# OpenHealth.net
KiCad netlist of a schematic drawn in EAGLE
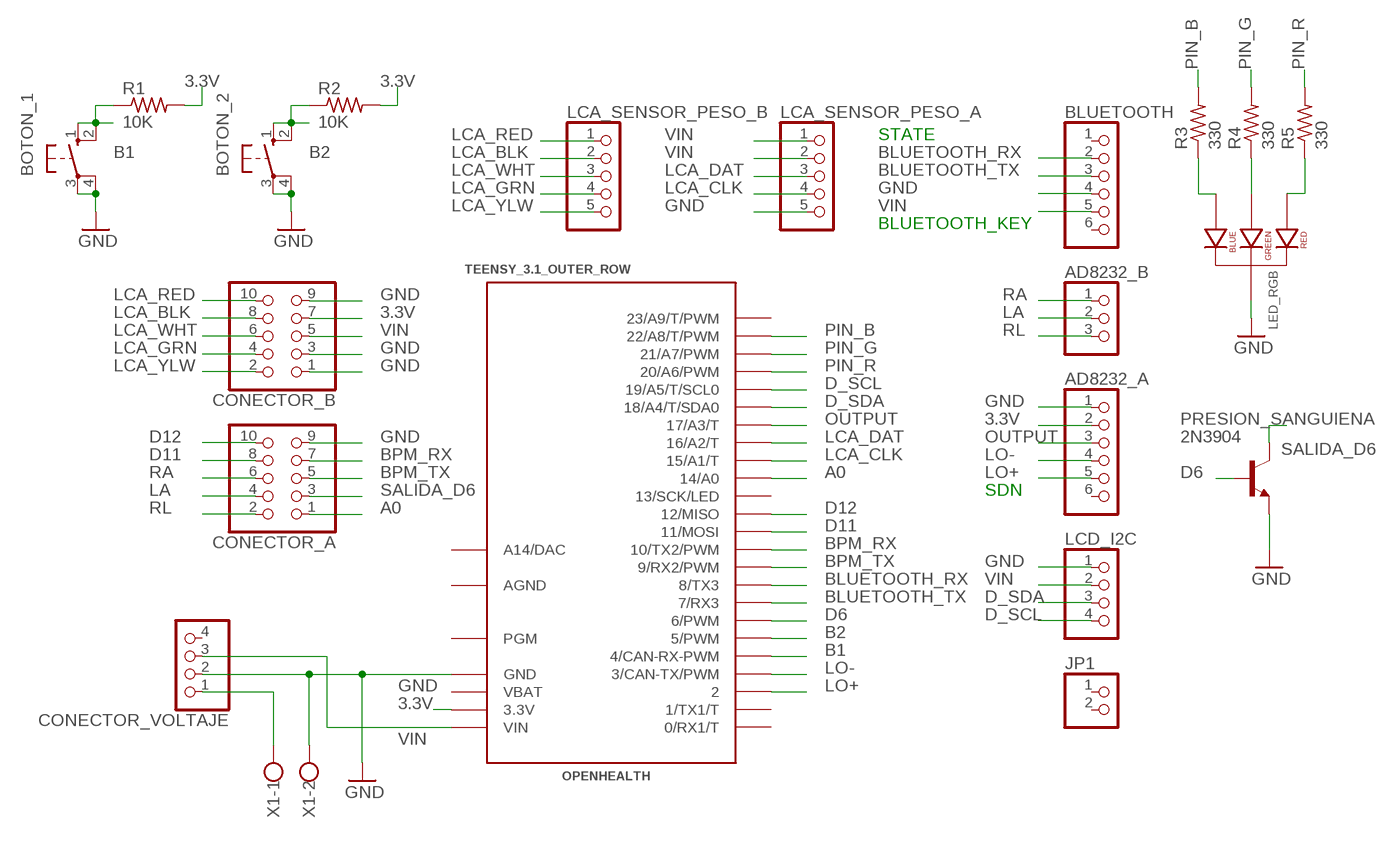
[diagram p0: schematic, sheet 1]

(export (version "E")
  (design (tool "Eeschema 10.0.6"))
  (components
    (comp (ref "AD8232_A")
      (value "PINHD-1X6")
      (footprint "eagle-import:1X06")
      (libsource (lib "eagle-import") (part "PINHD-1X6"))
    )
    (comp (ref "AD8232_B")
      (value "PINHD-1X3")
      (footprint "eagle-import:1X03")
      (libsource (lib "eagle-import") (part "PINHD-1X3"))
    )
    (comp (ref "BLUETOOTH")
      (value "PINHD-1X6")
      (footprint "eagle-import:1X06")
      (libsource (lib "eagle-import") (part "PINHD-1X6"))
    )
    (comp (ref "BOTON_1")
      (value "10-XX")
      (footprint "eagle-import:B3F-10XX")
      (fields (field (name "MPN") "B3F-1000"))
      (libsource (lib "eagle-import") (part "10-XX"))
    )
    (comp (ref "BOTON_2")
      (value "10-XX")
      (footprint "eagle-import:B3F-10XX")
      (fields (field (name "MPN") "B3F-1000"))
      (libsource (lib "eagle-import") (part "10-XX"))
    )
    (comp (ref "CONECTOR_A")
      (value "PINHD-2X5")
      (footprint "eagle-import:2X05")
      (libsource (lib "eagle-import") (part "PINHD-2X5"))
    )
    (comp (ref "CONECTOR_B")
      (value "PINHD-2X5")
      (footprint "eagle-import:2X05")
      (libsource (lib "eagle-import") (part "PINHD-2X5"))
    )
    (comp (ref "CONECTOR_VOLTAJE")
      (value "PINHD-1X4")
      (footprint "eagle-import:1X04")
      (libsource (lib "eagle-import") (part "PINHD-1X4"))
    )
    (comp (ref "JP1")
      (value "PINHD-1X2")
      (footprint "eagle-import:1X02")
      (libsource (lib "eagle-import") (part "PINHD-1X2"))
    )
    (comp (ref "LCA_SENSOR_PESO_A")
      (value "PINHD-1X5")
      (footprint "eagle-import:1X05")
      (libsource (lib "eagle-import") (part "PINHD-1X5"))
    )
    (comp (ref "LCA_SENSOR_PESO_B")
      (value "PINHD-1X5")
      (footprint "eagle-import:1X05")
      (libsource (lib "eagle-import") (part "PINHD-1X5"))
    )
    (comp (ref "LCD_I2C")
      (value "PINHD-1X4")
      (footprint "eagle-import:1X04")
      (libsource (lib "eagle-import") (part "PINHD-1X4"))
    )
    (comp (ref "LED_RGB")
      (value "LED-RGB-CC-THRUCLEAR")
      (footprint "eagle-import:LED-RGB-THRU")
      (libsource (lib "eagle-import") (part "LED-RGB-CC-THRUCLEAR"))
    )
    (comp (ref "OPENHEALTH")
      (value "TEENSY_3.1_OUTER_ROW")
      (footprint "eagle-import:TEENSY3-OUTER_ROW")
      (libsource (lib "eagle-import") (part "TEENSY_3.1_OUTER_ROW"))
    )
    (comp (ref "PRESION_SANGUIENA")
      (value "2N3904")
      (footprint "eagle-import:TO92")
      (libsource (lib "eagle-import") (part "2N3904"))
    )
    (comp (ref "R1")
      (value "10K")
      (footprint "eagle-import:0204_7")
      (libsource (lib "eagle-import") (part "R-US_0204/7"))
    )
    (comp (ref "R2")
      (value "10K")
      (footprint "eagle-import:0204_7")
      (libsource (lib "eagle-import") (part "R-US_0204/7"))
    )
    (comp (ref "R3")
      (value "330")
      (footprint "eagle-import:0204_7")
      (libsource (lib "eagle-import") (part "R-US_0204/7"))
    )
    (comp (ref "R4")
      (value "330")
      (footprint "eagle-import:0204_7")
      (libsource (lib "eagle-import") (part "R-US_0204/7"))
    )
    (comp (ref "R5")
      (value "330")
      (footprint "eagle-import:0204_7")
      (libsource (lib "eagle-import") (part "R-US_0204/7"))
    )
    (comp (ref "X1")
      (value "W237-102")
      (footprint "eagle-import:W237-102")
      (fields (field (name "MPN") "237-102"))
      (libsource (lib "eagle-import") (part "W237-102"))
    )
  )
  (nets
    (net (code "1") (name "/3.3V") (class "Default")
      (node (ref "AD8232_A") (pin "2") (pinfunction "2_2") (pintype "passive"))
      (node (ref "CONECTOR_B") (pin "7") (pinfunction "7_7") (pintype "passive"))
      (node (ref "OPENHEALTH") (pin "3.3V") (pinfunction "3.3V_3.3V") (pintype "power_in"))
      (node (ref "OPENHEALTH") (pin "3.3V1") (pinfunction "3.3V_3.3V1") (pintype "power_in"))
      (node (ref "R1") (pin "2") (pinfunction "2_2") (pintype "passive"))
      (node (ref "R2") (pin "2") (pinfunction "2_2") (pintype "passive"))
    )
    (net (code "2") (name "/A0") (class "Default")
      (node (ref "CONECTOR_A") (pin "1") (pinfunction "1_1") (pintype "passive"))
      (node (ref "OPENHEALTH") (pin "14/A0") (pinfunction "14/A0_14/A0") (pintype "bidirectional"))
    )
    (net (code "3") (name "/AGND") (class "Default")
      (node (ref "OPENHEALTH") (pin "AGND") (pinfunction "AGND_AGND") (pintype "power_in"))
    )
    (net (code "4") (name "/B1") (class "Default")
      (node (ref "BOTON_1") (pin "1") (pinfunction "S_1") (pintype "passive"))
      (node (ref "BOTON_1") (pin "2") (pinfunction "S1_2") (pintype "passive"))
      (node (ref "OPENHEALTH") (pin "4") (pinfunction "4/CAN-RX-PWM_4") (pintype "bidirectional"))
      (node (ref "R1") (pin "1") (pinfunction "1_1") (pintype "passive"))
    )
    (net (code "5") (name "/B2") (class "Default")
      (node (ref "BOTON_2") (pin "1") (pinfunction "S_1") (pintype "passive"))
      (node (ref "BOTON_2") (pin "2") (pinfunction "S1_2") (pintype "passive"))
      (node (ref "OPENHEALTH") (pin "5") (pinfunction "5/PWM_5") (pintype "bidirectional"))
      (node (ref "R2") (pin "1") (pinfunction "1_1") (pintype "passive"))
    )
    (net (code "6") (name "/BLUETOOTH_RX") (class "Default")
      (node (ref "BLUETOOTH") (pin "2") (pinfunction "2_2") (pintype "passive"))
      (node (ref "OPENHEALTH") (pin "8") (pinfunction "8/TX3_8") (pintype "bidirectional"))
    )
    (net (code "7") (name "/BLUETOOTH_TX") (class "Default")
      (node (ref "BLUETOOTH") (pin "3") (pinfunction "3_3") (pintype "passive"))
      (node (ref "OPENHEALTH") (pin "7") (pinfunction "7/RX3_7") (pintype "bidirectional"))
    )
    (net (code "8") (name "/BPM_RX") (class "Default")
      (node (ref "CONECTOR_A") (pin "7") (pinfunction "7_7") (pintype "passive"))
      (node (ref "OPENHEALTH") (pin "10") (pinfunction "10/TX2/PWM_10") (pintype "bidirectional"))
    )
    (net (code "9") (name "/BPM_TX") (class "Default")
      (node (ref "CONECTOR_A") (pin "5") (pinfunction "5_5") (pintype "passive"))
      (node (ref "OPENHEALTH") (pin "9") (pinfunction "9/RX2/PWM_9") (pintype "bidirectional"))
    )
    (net (code "10") (name "/D6") (class "Default")
      (node (ref "OPENHEALTH") (pin "6") (pinfunction "6/PWM_6") (pintype "bidirectional"))
      (node (ref "PRESION_SANGUIENA") (pin "2") (pinfunction "B_2") (pintype "passive"))
    )
    (net (code "11") (name "/D11") (class "Default")
      (node (ref "CONECTOR_A") (pin "8") (pinfunction "8_8") (pintype "passive"))
      (node (ref "OPENHEALTH") (pin "11") (pinfunction "11/MOSI_11") (pintype "bidirectional"))
    )
    (net (code "12") (name "/D12") (class "Default")
      (node (ref "CONECTOR_A") (pin "10") (pinfunction "10_10") (pintype "passive"))
      (node (ref "OPENHEALTH") (pin "12") (pinfunction "12/MISO_12") (pintype "bidirectional"))
    )
    (net (code "13") (name "/D_SCL") (class "Default")
      (node (ref "LCD_I2C") (pin "4") (pinfunction "4_4") (pintype "passive"))
      (node (ref "OPENHEALTH") (pin "19/A5") (pinfunction "19/A5/T/SCL0_19/A5") (pintype "bidirectional"))
    )
    (net (code "14") (name "/D_SDA") (class "Default")
      (node (ref "LCD_I2C") (pin "3") (pinfunction "3_3") (pintype "passive"))
      (node (ref "OPENHEALTH") (pin "18/A4") (pinfunction "18/A4/T/SDA0_18/A4") (pintype "bidirectional"))
    )
    (net (code "15") (name "/LA") (class "Default")
      (node (ref "AD8232_B") (pin "2") (pinfunction "2_2") (pintype "passive"))
      (node (ref "CONECTOR_A") (pin "4") (pinfunction "4_4") (pintype "passive"))
    )
    (net (code "16") (name "/LCA_BLK") (class "Default")
      (node (ref "CONECTOR_B") (pin "8") (pinfunction "8_8") (pintype "passive"))
      (node (ref "LCA_SENSOR_PESO_B") (pin "2") (pinfunction "2_2") (pintype "passive"))
    )
    (net (code "17") (name "/LCA_CLK") (class "Default")
      (node (ref "LCA_SENSOR_PESO_A") (pin "4") (pinfunction "4_4") (pintype "passive"))
      (node (ref "OPENHEALTH") (pin "15/A1") (pinfunction "15/A1/T_15/A1") (pintype "bidirectional"))
    )
    (net (code "18") (name "/LCA_DAT") (class "Default")
      (node (ref "LCA_SENSOR_PESO_A") (pin "3") (pinfunction "3_3") (pintype "passive"))
      (node (ref "OPENHEALTH") (pin "16/A2") (pinfunction "16/A2/T_16/A2") (pintype "bidirectional"))
    )
    (net (code "19") (name "/LCA_GRN") (class "Default")
      (node (ref "CONECTOR_B") (pin "4") (pinfunction "4_4") (pintype "passive"))
      (node (ref "LCA_SENSOR_PESO_B") (pin "4") (pinfunction "4_4") (pintype "passive"))
    )
    (net (code "20") (name "/LCA_RED") (class "Default")
      (node (ref "CONECTOR_B") (pin "10") (pinfunction "10_10") (pintype "passive"))
      (node (ref "LCA_SENSOR_PESO_B") (pin "1") (pinfunction "1_1") (pintype "passive"))
    )
    (net (code "21") (name "/LCA_WHT") (class "Default")
      (node (ref "CONECTOR_B") (pin "6") (pinfunction "6_6") (pintype "passive"))
      (node (ref "LCA_SENSOR_PESO_B") (pin "3") (pinfunction "3_3") (pintype "passive"))
    )
    (net (code "22") (name "/LCA_YLW") (class "Default")
      (node (ref "CONECTOR_B") (pin "2") (pinfunction "2_2") (pintype "passive"))
      (node (ref "LCA_SENSOR_PESO_B") (pin "5") (pinfunction "5_5") (pintype "passive"))
    )
    (net (code "23") (name "/LO+") (class "Default")
      (node (ref "AD8232_A") (pin "5") (pinfunction "5_5") (pintype "passive"))
      (node (ref "OPENHEALTH") (pin "2") (pinfunction "2_2") (pintype "bidirectional"))
    )
    (net (code "24") (name "/LO-") (class "Default")
      (node (ref "AD8232_A") (pin "4") (pinfunction "4_4") (pintype "passive"))
      (node (ref "OPENHEALTH") (pin "3") (pinfunction "3/CAN-TX/PWM_3") (pintype "bidirectional"))
    )
    (net (code "25") (name "/OUTPUT") (class "Default")
      (node (ref "AD8232_A") (pin "3") (pinfunction "3_3") (pintype "passive"))
      (node (ref "OPENHEALTH") (pin "17/A3") (pinfunction "17/A3/T_17/A3") (pintype "bidirectional"))
    )
    (net (code "26") (name "/PIN_B") (class "Default")
      (node (ref "OPENHEALTH") (pin "22/A8") (pinfunction "22/A8/T/PWM_22/A8") (pintype "bidirectional"))
      (node (ref "R3") (pin "2") (pinfunction "2_2") (pintype "passive"))
    )
    (net (code "27") (name "/PIN_G") (class "Default")
      (node (ref "OPENHEALTH") (pin "21/A7") (pinfunction "21/A7/PWM_21/A7") (pintype "bidirectional"))
      (node (ref "R4") (pin "2") (pinfunction "2_2") (pintype "passive"))
    )
    (net (code "28") (name "/PIN_R") (class "Default")
      (node (ref "OPENHEALTH") (pin "20/A6") (pinfunction "20/A6/PWM_20/A6") (pintype "bidirectional"))
      (node (ref "R5") (pin "2") (pinfunction "2_2") (pintype "passive"))
    )
    (net (code "29") (name "/RA") (class "Default")
      (node (ref "AD8232_B") (pin "1") (pinfunction "1_1") (pintype "passive"))
      (node (ref "CONECTOR_A") (pin "6") (pinfunction "6_6") (pintype "passive"))
    )
    (net (code "30") (name "/RL") (class "Default")
      (node (ref "AD8232_B") (pin "3") (pinfunction "3_3") (pintype "passive"))
      (node (ref "CONECTOR_A") (pin "2") (pinfunction "2_2") (pintype "passive"))
    )
    (net (code "31") (name "/SALIDA_D6") (class "Default")
      (node (ref "CONECTOR_A") (pin "3") (pinfunction "3_3") (pintype "passive"))
      (node (ref "PRESION_SANGUIENA") (pin "1") (pinfunction "C_1") (pintype "passive"))
    )
    (net (code "32") (name "/VBAT") (class "Default")
      (node (ref "OPENHEALTH") (pin "VBAT") (pinfunction "VBAT_VBAT") (pintype "power_in"))
    )
    (net (code "33") (name "/VIN") (class "Default")
      (node (ref "BLUETOOTH") (pin "5") (pinfunction "5_5") (pintype "passive"))
      (node (ref "CONECTOR_B") (pin "5") (pinfunction "5_5") (pintype "passive"))
      (node (ref "CONECTOR_VOLTAJE") (pin "3") (pinfunction "3_3") (pintype "passive"))
      (node (ref "LCA_SENSOR_PESO_A") (pin "1") (pinfunction "1_1") (pintype "passive"))
      (node (ref "LCA_SENSOR_PESO_A") (pin "2") (pinfunction "2_2") (pintype "passive"))
      (node (ref "LCD_I2C") (pin "2") (pinfunction "2_2") (pintype "passive"))
      (node (ref "OPENHEALTH") (pin "VIN") (pinfunction "VIN_VIN") (pintype "power_in"))
    )
    (net (code "34") (name "GND") (class "Default")
      (node (ref "AD8232_A") (pin "1") (pinfunction "1_1") (pintype "passive"))
      (node (ref "BLUETOOTH") (pin "4") (pinfunction "4_4") (pintype "passive"))
      (node (ref "BOTON_1") (pin "3") (pinfunction "P_3") (pintype "passive"))
      (node (ref "BOTON_1") (pin "4") (pinfunction "P1_4") (pintype "passive"))
      (node (ref "BOTON_2") (pin "3") (pinfunction "P_3") (pintype "passive"))
      (node (ref "BOTON_2") (pin "4") (pinfunction "P1_4") (pintype "passive"))
      (node (ref "CONECTOR_A") (pin "9") (pinfunction "9_9") (pintype "passive"))
      (node (ref "CONECTOR_B") (pin "1") (pinfunction "1_1") (pintype "passive"))
      (node (ref "CONECTOR_B") (pin "3") (pinfunction "3_3") (pintype "passive"))
      (node (ref "CONECTOR_B") (pin "9") (pinfunction "9_9") (pintype "passive"))
      (node (ref "CONECTOR_VOLTAJE") (pin "2") (pinfunction "2_2") (pintype "passive"))
      (node (ref "LCA_SENSOR_PESO_A") (pin "5") (pinfunction "5_5") (pintype "passive"))
      (node (ref "LCD_I2C") (pin "1") (pinfunction "1_1") (pintype "passive"))
      (node (ref "LED_RGB") (pin "2") (pinfunction "CATHODE_2") (pintype "bidirectional"))
      (node (ref "OPENHEALTH") (pin "GND") (pinfunction "GND_GND") (pintype "power_in"))
      (node (ref "OPENHEALTH") (pin "GND1") (pinfunction "GND_GND1") (pintype "power_in"))
      (node (ref "PRESION_SANGUIENA") (pin "3") (pinfunction "E_3") (pintype "passive"))
      (node (ref "X1") (pin "2") (pinfunction "KL_2") (pintype "passive"))
    )
    (net (code "35") (name "Net-(LED_RGB-BLUE_CATHODE)") (class "Default")
      (node (ref "LED_RGB") (pin "4") (pinfunction "BLUE_CATHODE_4") (pintype "bidirectional"))
      (node (ref "R3") (pin "1") (pinfunction "1_1") (pintype "passive"))
    )
    (net (code "36") (name "Net-(LED_RGB-GREEN_CATHODE)") (class "Default")
      (node (ref "LED_RGB") (pin "3") (pinfunction "GREEN_CATHODE_3") (pintype "bidirectional"))
      (node (ref "R4") (pin "1") (pinfunction "1_1") (pintype "passive"))
    )
    (net (code "37") (name "Net-(LED_RGB-RED_CATHODE)") (class "Default")
      (node (ref "LED_RGB") (pin "1") (pinfunction "RED_CATHODE_1") (pintype "bidirectional"))
      (node (ref "R5") (pin "1") (pinfunction "1_1") (pintype "passive"))
    )
    (net (code "38") (name "Net-(X1A-KL)") (class "Default")
      (node (ref "CONECTOR_VOLTAJE") (pin "1") (pinfunction "1_1") (pintype "passive"))
      (node (ref "X1") (pin "1") (pinfunction "KL_1") (pintype "passive"))
    )
    (net (code "39") (name "unconnected-(AD8232_A-Pad6)") (class "Default")
      (node (ref "AD8232_A") (pin "6") (pinfunction "6_6") (pintype "passive"))
    )
    (net (code "40") (name "unconnected-(BLUETOOTH-Pad1)") (class "Default")
      (node (ref "BLUETOOTH") (pin "1") (pinfunction "1_1") (pintype "passive"))
    )
    (net (code "41") (name "unconnected-(BLUETOOTH-Pad6)") (class "Default")
      (node (ref "BLUETOOTH") (pin "6") (pinfunction "6_6") (pintype "passive"))
    )
    (net (code "42") (name "unconnected-(CONECTOR_VOLTAJE-Pad4)") (class "Default")
      (node (ref "CONECTOR_VOLTAJE") (pin "4") (pinfunction "4_4") (pintype "passive"))
    )
    (net (code "43") (name "unconnected-(JP1-Pad1)") (class "Default")
      (node (ref "JP1") (pin "1") (pinfunction "1_1") (pintype "passive"))
    )
    (net (code "44") (name "unconnected-(JP1-Pad2)") (class "Default")
      (node (ref "JP1") (pin "2") (pinfunction "2_2") (pintype "passive"))
    )
    (net (code "45") (name "unconnected-(OPENHEALTH-0{slash}RX1{slash}T-Pad0)") (class "Default")
      (node (ref "OPENHEALTH") (pin "0") (pinfunction "0/RX1/T_0") (pintype "bidirectional"))
    )
    (net (code "46") (name "unconnected-(OPENHEALTH-1{slash}TX1{slash}T-Pad1)") (class "Default")
      (node (ref "OPENHEALTH") (pin "1") (pinfunction "1/TX1/T_1") (pintype "bidirectional"))
    )
    (net (code "47") (name "unconnected-(OPENHEALTH-13{slash}SCK{slash}LED-Pad13)") (class "Default")
      (node (ref "OPENHEALTH") (pin "13") (pinfunction "13/SCK/LED_13") (pintype "bidirectional"))
    )
    (net (code "48") (name "unconnected-(OPENHEALTH-23{slash}A9{slash}T{slash}PWM-Pad23{slash}A9)") (class "Default")
      (node (ref "OPENHEALTH") (pin "23/A9") (pinfunction "23/A9/T/PWM_23/A9") (pintype "bidirectional"))
    )
    (net (code "49") (name "unconnected-(OPENHEALTH-A14{slash}DAC-PadRESET{slash}DAC)") (class "Default")
      (node (ref "OPENHEALTH") (pin "RESET/DAC") (pinfunction "A14/DAC_RESET/DAC") (pintype "bidirectional"))
    )
    (net (code "50") (name "unconnected-(OPENHEALTH-PadPGM)") (class "Default")
      (node (ref "OPENHEALTH") (pin "PGM") (pinfunction "PGM_PGM") (pintype "bidirectional"))
    )
  )
)
